# button_microcontroller_side.net
KiCad netlist of a schematic drawn in EAGLE
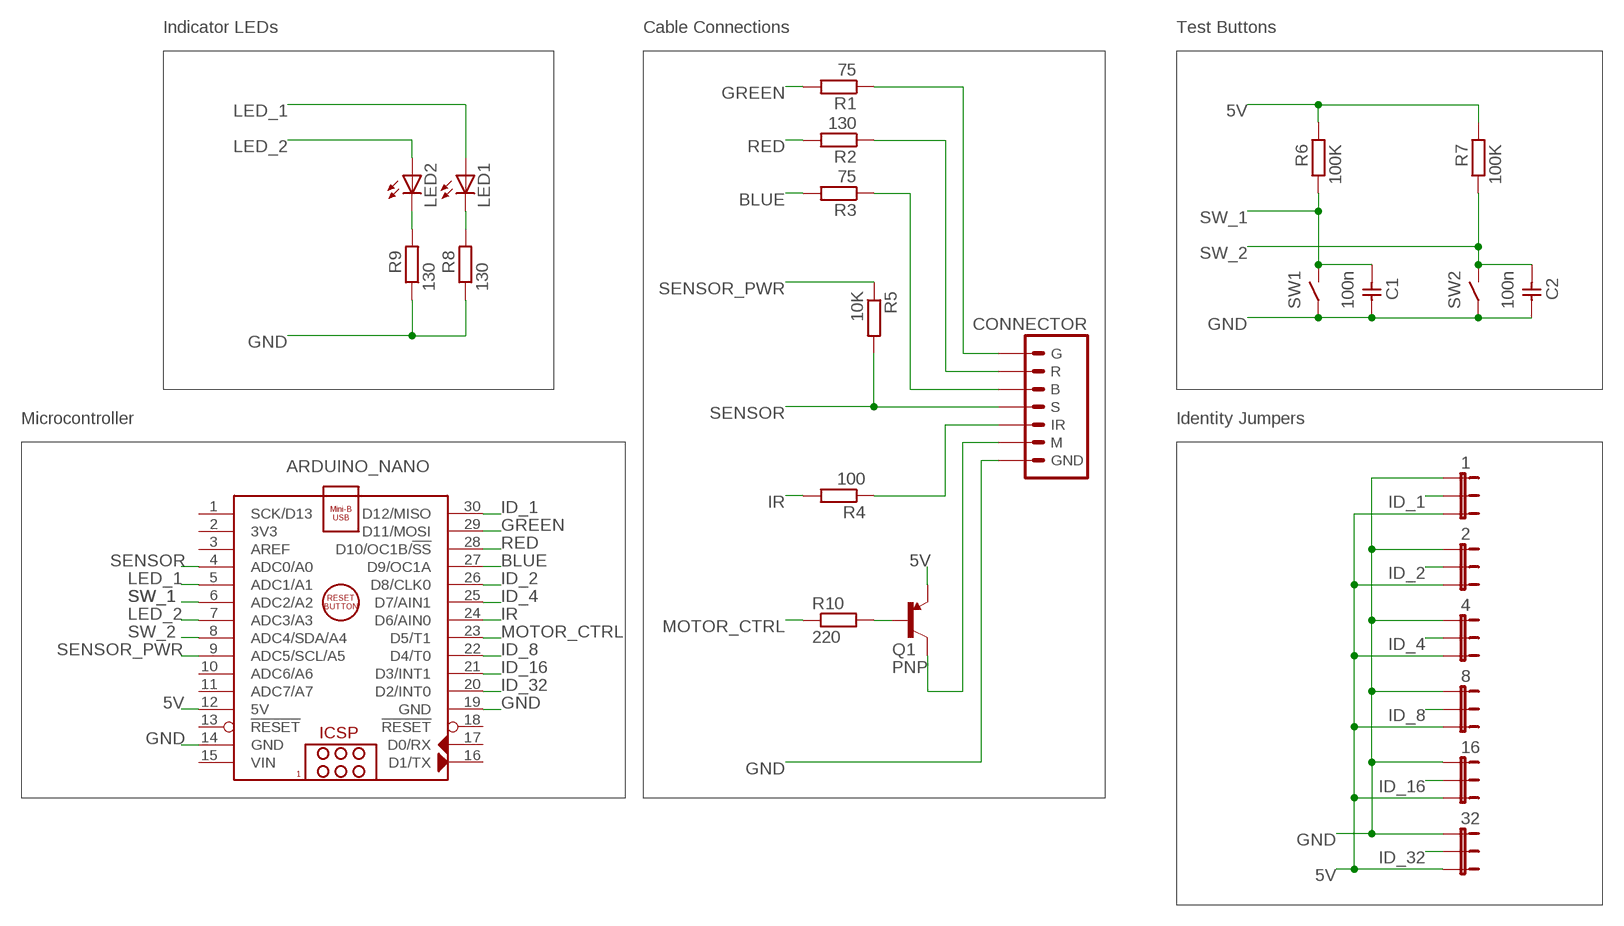
[diagram p0: schematic, sheet 1]

(export (version "E")
  (design (tool "Eeschema 10.0.6"))
  (components
    (comp (ref "1")
      (value "JP2E")
      (footprint "eagle-import:JP2")
      (libsource (lib "eagle-import") (part "JP2E"))
    )
    (comp (ref "2")
      (value "JP2E")
      (footprint "eagle-import:JP2")
      (libsource (lib "eagle-import") (part "JP2E"))
    )
    (comp (ref "4")
      (value "JP2E")
      (footprint "eagle-import:JP2")
      (libsource (lib "eagle-import") (part "JP2E"))
    )
    (comp (ref "8")
      (value "JP2E")
      (footprint "eagle-import:JP2")
      (libsource (lib "eagle-import") (part "JP2E"))
    )
    (comp (ref "16")
      (value "JP2E")
      (footprint "eagle-import:JP2")
      (libsource (lib "eagle-import") (part "JP2E"))
    )
    (comp (ref "32")
      (value "JP2E")
      (footprint "eagle-import:JP2")
      (libsource (lib "eagle-import") (part "JP2E"))
    )
    (comp (ref "ARDUINO_NANO")
      (value "ARDUINO_NANO")
      (footprint "eagle-import:ARDUINO_NANO")
      (libsource (lib "eagle-import") (part "ARDUINO_NANO"))
    )
    (comp (ref "C1")
      (value "100n")
      (footprint "eagle-import:CAPACITOR")
      (libsource (lib "eagle-import") (part "CAPACITOR"))
    )
    (comp (ref "C2")
      (value "100n")
      (footprint "eagle-import:CAPACITOR")
      (libsource (lib "eagle-import") (part "CAPACITOR"))
    )
    (comp (ref "CONNECTOR")
      (value "CONNECTOR_PADSHOLES")
      (footprint "eagle-import:CONNECTOR_ARDUINO_SIDE")
      (libsource (lib "eagle-import") (part "CONNECTOR_PADSHOLES"))
    )
    (comp (ref "LED1")
      (value "LED_3MM")
      (footprint "eagle-import:TCR5000_IR_EMITTER")
      (libsource (lib "eagle-import") (part "LED_3MM"))
    )
    (comp (ref "LED2")
      (value "LED_3MM")
      (footprint "eagle-import:TCR5000_IR_EMITTER")
      (libsource (lib "eagle-import") (part "LED_3MM"))
    )
    (comp (ref "Q1")
      (value "PNP")
      (footprint "eagle-import:TO92-")
      (libsource (lib "eagle-import") (part "PNP"))
    )
    (comp (ref "R1")
      (value "75")
      (footprint "eagle-import:0204_7")
      (libsource (lib "eagle-import") (part "R-EU_0204/7"))
    )
    (comp (ref "R2")
      (value "130")
      (footprint "eagle-import:0204_7")
      (libsource (lib "eagle-import") (part "R-EU_0204/7"))
    )
    (comp (ref "R3")
      (value "75")
      (footprint "eagle-import:0204_7")
      (libsource (lib "eagle-import") (part "R-EU_0204/7"))
    )
    (comp (ref "R4")
      (value "100")
      (footprint "eagle-import:0204_7")
      (libsource (lib "eagle-import") (part "R-EU_0204/7"))
    )
    (comp (ref "R5")
      (value "10K")
      (footprint "eagle-import:0204_7")
      (libsource (lib "eagle-import") (part "R-EU_0204/7"))
    )
    (comp (ref "R6")
      (value "100K")
      (footprint "eagle-import:0204_7")
      (libsource (lib "eagle-import") (part "R-EU_0204/7"))
    )
    (comp (ref "R7")
      (value "100K")
      (footprint "eagle-import:0204_7")
      (libsource (lib "eagle-import") (part "R-EU_0204/7"))
    )
    (comp (ref "R8")
      (value "130")
      (footprint "eagle-import:0204_7")
      (libsource (lib "eagle-import") (part "R-EU_0204/7"))
    )
    (comp (ref "R9")
      (value "130")
      (footprint "eagle-import:0204_7")
      (libsource (lib "eagle-import") (part "R-EU_0204/7"))
    )
    (comp (ref "R10")
      (value "220")
      (footprint "eagle-import:0204_7")
      (libsource (lib "eagle-import") (part "R-EU_0204/7"))
    )
    (comp (ref "SW1")
      (value "BUTTON")
      (footprint "eagle-import:KS-01Q-01_BUTTON")
      (libsource (lib "eagle-import") (part "BUTTON"))
    )
    (comp (ref "SW2")
      (value "BUTTON")
      (footprint "eagle-import:KS-01Q-01_BUTTON")
      (libsource (lib "eagle-import") (part "BUTTON"))
    )
  )
  (nets
    (net (code "1") (name "/5V") (class "Default")
      (node (ref "1") (pin "3") (pinfunction "3_3") (pintype "passive"))
      (node (ref "16") (pin "3") (pinfunction "3_3") (pintype "passive"))
      (node (ref "2") (pin "3") (pinfunction "3_3") (pintype "passive"))
      (node (ref "32") (pin "3") (pinfunction "3_3") (pintype "passive"))
      (node (ref "4") (pin "3") (pinfunction "3_3") (pintype "passive"))
      (node (ref "8") (pin "3") (pinfunction "3_3") (pintype "passive"))
      (node (ref "ARDUINO_NANO") (pin "12") (pinfunction "5V_12") (pintype "power_in"))
      (node (ref "Q1") (pin "E") (pinfunction "E_E") (pintype "passive"))
      (node (ref "R6") (pin "2") (pinfunction "2_2") (pintype "passive"))
      (node (ref "R7") (pin "2") (pinfunction "2_2") (pintype "passive"))
    )
    (net (code "2") (name "/BLUE") (class "Default")
      (node (ref "ARDUINO_NANO") (pin "27") (pinfunction "D9/OC1A_27") (pintype "bidirectional"))
      (node (ref "R3") (pin "2") (pinfunction "2_2") (pintype "passive"))
    )
    (net (code "3") (name "/GND") (class "Default")
      (node (ref "1") (pin "1") (pinfunction "1_1") (pintype "passive"))
      (node (ref "16") (pin "1") (pinfunction "1_1") (pintype "passive"))
      (node (ref "2") (pin "1") (pinfunction "1_1") (pintype "passive"))
      (node (ref "32") (pin "1") (pinfunction "1_1") (pintype "passive"))
      (node (ref "4") (pin "1") (pinfunction "1_1") (pintype "passive"))
      (node (ref "8") (pin "1") (pinfunction "1_1") (pintype "passive"))
      (node (ref "ARDUINO_NANO") (pin "14") (pinfunction "GND_14") (pintype "power_in"))
      (node (ref "ARDUINO_NANO") (pin "19") (pinfunction "GND_19") (pintype "power_in"))
      (node (ref "C1") (pin "P$1") (pinfunction "1_P$1") (pintype "passive"))
      (node (ref "C2") (pin "P$1") (pinfunction "1_P$1") (pintype "passive"))
      (node (ref "CONNECTOR") (pin "GND") (pinfunction "GND_GND") (pintype "passive"))
      (node (ref "R8") (pin "1") (pinfunction "1_1") (pintype "passive"))
      (node (ref "R9") (pin "1") (pinfunction "1_1") (pintype "passive"))
      (node (ref "SW1") (pin "1") (pinfunction "1_1") (pintype "passive"))
      (node (ref "SW1") (pin "3") (pinfunction "1_3") (pintype "passive"))
      (node (ref "SW2") (pin "1") (pinfunction "1_1") (pintype "passive"))
      (node (ref "SW2") (pin "3") (pinfunction "1_3") (pintype "passive"))
    )
    (net (code "4") (name "/GREEN") (class "Default")
      (node (ref "ARDUINO_NANO") (pin "29") (pinfunction "D11/MOSI_29") (pintype "bidirectional"))
      (node (ref "R1") (pin "2") (pinfunction "2_2") (pintype "passive"))
    )
    (net (code "5") (name "/ID_1") (class "Default")
      (node (ref "1") (pin "2") (pinfunction "2_2") (pintype "passive"))
      (node (ref "ARDUINO_NANO") (pin "30") (pinfunction "D12/MISO_30") (pintype "bidirectional"))
    )
    (net (code "6") (name "/ID_2") (class "Default")
      (node (ref "2") (pin "2") (pinfunction "2_2") (pintype "passive"))
      (node (ref "ARDUINO_NANO") (pin "26") (pinfunction "D8/CLK0_26") (pintype "bidirectional"))
    )
    (net (code "7") (name "/ID_4") (class "Default")
      (node (ref "4") (pin "2") (pinfunction "2_2") (pintype "passive"))
      (node (ref "ARDUINO_NANO") (pin "25") (pinfunction "D7/AIN1_25") (pintype "bidirectional"))
    )
    (net (code "8") (name "/ID_8") (class "Default")
      (node (ref "8") (pin "2") (pinfunction "2_2") (pintype "passive"))
      (node (ref "ARDUINO_NANO") (pin "22") (pinfunction "D4/T0_22") (pintype "bidirectional"))
    )
    (net (code "9") (name "/ID_16") (class "Default")
      (node (ref "16") (pin "2") (pinfunction "2_2") (pintype "passive"))
      (node (ref "ARDUINO_NANO") (pin "21") (pinfunction "D3/INT1_21") (pintype "bidirectional"))
    )
    (net (code "10") (name "/ID_32") (class "Default")
      (node (ref "32") (pin "2") (pinfunction "2_2") (pintype "passive"))
      (node (ref "ARDUINO_NANO") (pin "20") (pinfunction "D2/INT0_20") (pintype "bidirectional"))
    )
    (net (code "11") (name "/IR") (class "Default")
      (node (ref "ARDUINO_NANO") (pin "24") (pinfunction "D6/AIN0_24") (pintype "bidirectional"))
      (node (ref "R4") (pin "2") (pinfunction "2_2") (pintype "passive"))
    )
    (net (code "12") (name "/LED_1") (class "Default")
      (node (ref "ARDUINO_NANO") (pin "5") (pinfunction "ADC1/A1_5") (pintype "bidirectional"))
      (node (ref "LED1") (pin "A") (pinfunction "A_A") (pintype "passive"))
    )
    (net (code "13") (name "/LED_2") (class "Default")
      (node (ref "ARDUINO_NANO") (pin "7") (pinfunction "ADC3/A3_7") (pintype "bidirectional"))
      (node (ref "LED2") (pin "A") (pinfunction "A_A") (pintype "passive"))
    )
    (net (code "14") (name "/MOTOR_CTRL") (class "Default")
      (node (ref "ARDUINO_NANO") (pin "23") (pinfunction "D5/T1_23") (pintype "bidirectional"))
      (node (ref "R10") (pin "1") (pinfunction "1_1") (pintype "passive"))
    )
    (net (code "15") (name "/RED") (class "Default")
      (node (ref "ARDUINO_NANO") (pin "28") (pinfunction "D10/OC1B/~{SS}_28") (pintype "bidirectional"))
      (node (ref "R2") (pin "2") (pinfunction "2_2") (pintype "passive"))
    )
    (net (code "16") (name "/SENSOR") (class "Default")
      (node (ref "ARDUINO_NANO") (pin "4") (pinfunction "ADC0/A0_4") (pintype "bidirectional"))
      (node (ref "CONNECTOR") (pin "S") (pinfunction "S_S") (pintype "passive"))
      (node (ref "R5") (pin "2") (pinfunction "2_2") (pintype "passive"))
    )
    (net (code "17") (name "/SENSOR_PWR") (class "Default")
      (node (ref "ARDUINO_NANO") (pin "9") (pinfunction "ADC5/SCL/A5_9") (pintype "bidirectional"))
      (node (ref "R5") (pin "1") (pinfunction "1_1") (pintype "passive"))
    )
    (net (code "18") (name "/SW_1") (class "Default")
      (node (ref "ARDUINO_NANO") (pin "6") (pinfunction "ADC2/A2_6") (pintype "bidirectional"))
      (node (ref "C1") (pin "P$2") (pinfunction "2_P$2") (pintype "passive"))
      (node (ref "R6") (pin "1") (pinfunction "1_1") (pintype "passive"))
      (node (ref "SW1") (pin "2") (pinfunction "2_2") (pintype "passive"))
      (node (ref "SW1") (pin "4") (pinfunction "2_4") (pintype "passive"))
    )
    (net (code "19") (name "/SW_2") (class "Default")
      (node (ref "ARDUINO_NANO") (pin "8") (pinfunction "ADC4/SDA/A4_8") (pintype "bidirectional"))
      (node (ref "C2") (pin "P$2") (pinfunction "2_P$2") (pintype "passive"))
      (node (ref "R7") (pin "1") (pinfunction "1_1") (pintype "passive"))
      (node (ref "SW2") (pin "2") (pinfunction "2_2") (pintype "passive"))
      (node (ref "SW2") (pin "4") (pinfunction "2_4") (pintype "passive"))
    )
    (net (code "20") (name "/VIN") (class "Default")
      (node (ref "ARDUINO_NANO") (pin "15") (pinfunction "VIN_15") (pintype "power_in"))
    )
    (net (code "21") (name "Net-(CONNECTOR-PadB)") (class "Default")
      (node (ref "CONNECTOR") (pin "B") (pinfunction "B_B") (pintype "passive"))
      (node (ref "R3") (pin "1") (pinfunction "1_1") (pintype "passive"))
    )
    (net (code "22") (name "Net-(CONNECTOR-PadG)") (class "Default")
      (node (ref "CONNECTOR") (pin "G") (pinfunction "G_G") (pintype "passive"))
      (node (ref "R1") (pin "1") (pinfunction "1_1") (pintype "passive"))
    )
    (net (code "23") (name "Net-(CONNECTOR-PadIR)") (class "Default")
      (node (ref "CONNECTOR") (pin "IR") (pinfunction "IR_IR") (pintype "passive"))
      (node (ref "R4") (pin "1") (pinfunction "1_1") (pintype "passive"))
    )
    (net (code "24") (name "Net-(CONNECTOR-PadM)") (class "Default")
      (node (ref "CONNECTOR") (pin "M") (pinfunction "M_M") (pintype "passive"))
      (node (ref "Q1") (pin "C") (pinfunction "C_C") (pintype "passive"))
    )
    (net (code "25") (name "Net-(CONNECTOR-PadR)") (class "Default")
      (node (ref "CONNECTOR") (pin "R") (pinfunction "R_R") (pintype "passive"))
      (node (ref "R2") (pin "1") (pinfunction "1_1") (pintype "passive"))
    )
    (net (code "26") (name "Net-(LED1-PadC)") (class "Default")
      (node (ref "LED1") (pin "C") (pinfunction "C_C") (pintype "passive"))
      (node (ref "R8") (pin "2") (pinfunction "2_2") (pintype "passive"))
    )
    (net (code "27") (name "Net-(LED2-PadC)") (class "Default")
      (node (ref "LED2") (pin "C") (pinfunction "C_C") (pintype "passive"))
      (node (ref "R9") (pin "2") (pinfunction "2_2") (pintype "passive"))
    )
    (net (code "28") (name "Net-(Q1-PadB)") (class "Default")
      (node (ref "Q1") (pin "B") (pinfunction "B_B") (pintype "passive"))
      (node (ref "R10") (pin "2") (pinfunction "2_2") (pintype "passive"))
    )
    (net (code "29") (name "unconnected-(ARDUINO_NANO-3V3-Pad2)") (class "Default")
      (node (ref "ARDUINO_NANO") (pin "2") (pinfunction "3V3_2") (pintype "output"))
    )
    (net (code "30") (name "unconnected-(ARDUINO_NANO-ADC6{slash}A6-Pad10)") (class "Default")
      (node (ref "ARDUINO_NANO") (pin "10") (pinfunction "ADC6/A6_10") (pintype "bidirectional"))
    )
    (net (code "31") (name "unconnected-(ARDUINO_NANO-ADC7{slash}A7-Pad11)") (class "Default")
      (node (ref "ARDUINO_NANO") (pin "11") (pinfunction "ADC7/A7_11") (pintype "bidirectional"))
    )
    (net (code "32") (name "unconnected-(ARDUINO_NANO-AREF-Pad3)") (class "Default")
      (node (ref "ARDUINO_NANO") (pin "3") (pinfunction "AREF_3") (pintype "input"))
    )
    (net (code "33") (name "unconnected-(ARDUINO_NANO-D0{slash}RX-Pad17)") (class "Default")
      (node (ref "ARDUINO_NANO") (pin "17") (pinfunction "D0/RX_17") (pintype "bidirectional"))
    )
    (net (code "34") (name "unconnected-(ARDUINO_NANO-D1{slash}TX-Pad16)") (class "Default")
      (node (ref "ARDUINO_NANO") (pin "16") (pinfunction "D1/TX_16") (pintype "bidirectional"))
    )
    (net (code "35") (name "unconnected-(ARDUINO_NANO-SCK{slash}D13-Pad1)") (class "Default")
      (node (ref "ARDUINO_NANO") (pin "1") (pinfunction "SCK/D13_1") (pintype "bidirectional"))
    )
    (net (code "36") (name "unconnected-(ARDUINO_NANO-~{RESET}-Pad13)") (class "Default")
      (node (ref "ARDUINO_NANO") (pin "13") (pinfunction "~{RESET}_13") (pintype "input"))
    )
    (net (code "37") (name "unconnected-(ARDUINO_NANO-~{RESET}-Pad18)") (class "Default")
      (node (ref "ARDUINO_NANO") (pin "18") (pinfunction "~{RESET}_18") (pintype "input"))
    )
  )
)
